# 10_-_ETHERNET.net
KiCad netlist of a schematic drawn in Altium Designer
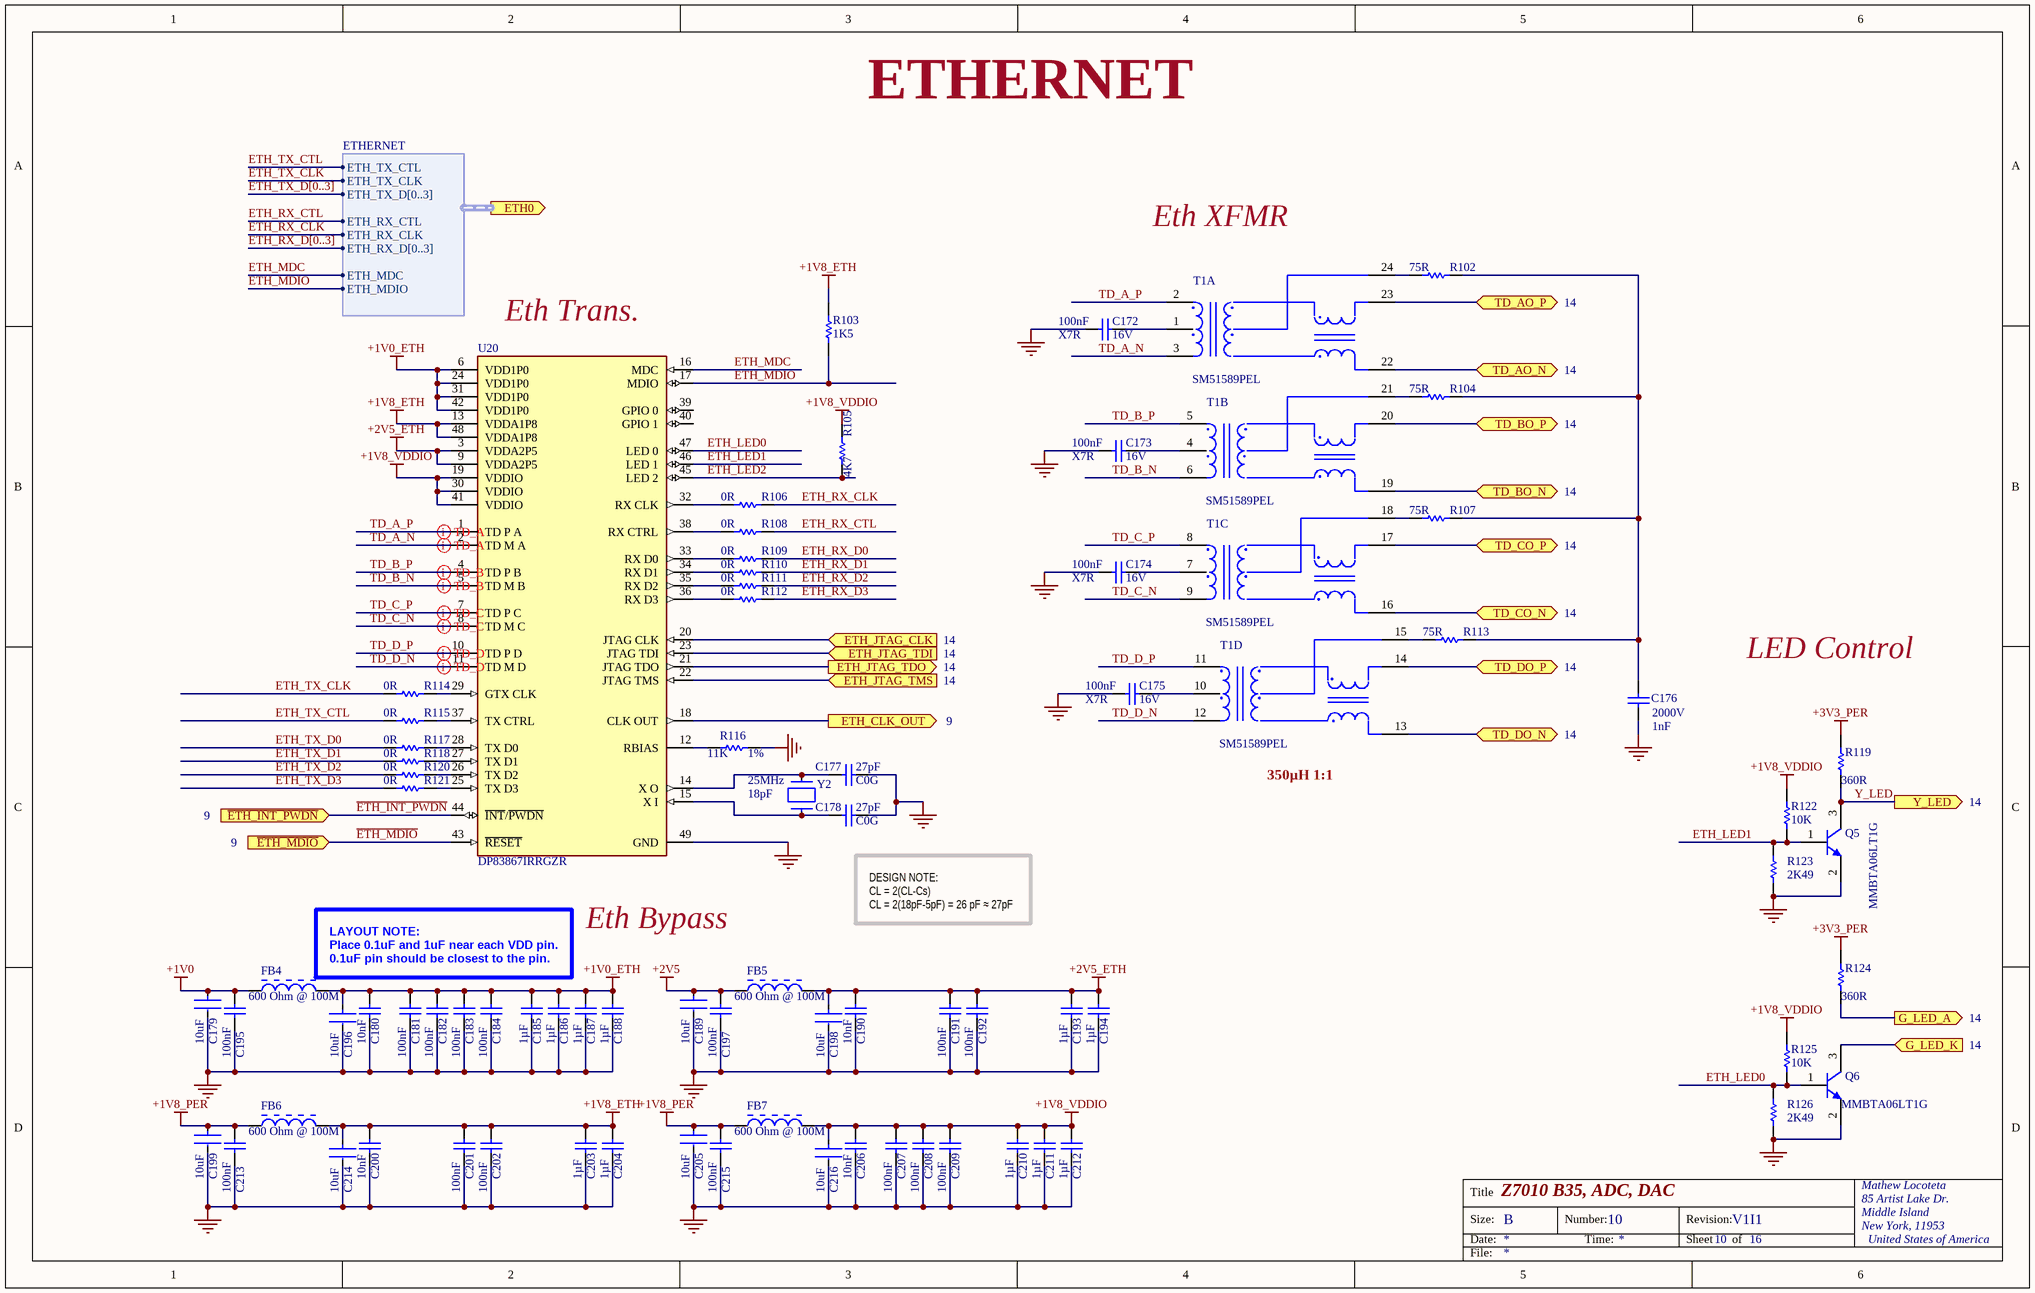
[diagram p0: [10] - ETHERNET.SchDoc]

(export (version "E")
  (design (tool "Eeschema 10.0.6"))
  (components
    (comp (ref "C172")
      (value "100nF 0402 16V")
      (fields
        (field (name "MANUFACTURER") "KEMET")
        (field (name "MANUFACTURER PART NUMBER") "C0402C104J4RACTU")
        (field (name "TOLERANCE") "5%")
        (field (name "DIELECTRIC") "X7R")
        (field (name "VOLTAGE RATING") "16V")
        (field (name "CAPACITANCE") "100nF")
      )
      (libsource (lib "Zynq 7000") (part "C0402C104J4RACTU"))
    )
    (comp (ref "C173")
      (value "100nF 0402 16V")
      (fields
        (field (name "MANUFACTURER") "KEMET")
        (field (name "MANUFACTURER PART NUMBER") "C0402C104J4RACTU")
        (field (name "TOLERANCE") "5%")
        (field (name "DIELECTRIC") "X7R")
        (field (name "VOLTAGE RATING") "16V")
        (field (name "CAPACITANCE") "100nF")
      )
      (libsource (lib "Zynq 7000") (part "C0402C104J4RACTU"))
    )
    (comp (ref "C174")
      (value "100nF 0402 16V")
      (fields
        (field (name "MANUFACTURER") "KEMET")
        (field (name "MANUFACTURER PART NUMBER") "C0402C104J4RACTU")
        (field (name "TOLERANCE") "5%")
        (field (name "DIELECTRIC") "X7R")
        (field (name "VOLTAGE RATING") "16V")
        (field (name "CAPACITANCE") "100nF")
      )
      (libsource (lib "Zynq 7000") (part "C0402C104J4RACTU"))
    )
    (comp (ref "C175")
      (value "100nF 0402 16V")
      (fields
        (field (name "MANUFACTURER") "KEMET")
        (field (name "MANUFACTURER PART NUMBER") "C0402C104J4RACTU")
        (field (name "TOLERANCE") "5%")
        (field (name "DIELECTRIC") "X7R")
        (field (name "VOLTAGE RATING") "16V")
        (field (name "CAPACITANCE") "100nF")
      )
      (libsource (lib "Zynq 7000") (part "C0402C104J4RACTU"))
    )
    (comp (ref "C176")
      (value "1808GC102KAT1A")
      (footprint "CAPC4620X180X75LL50T35")
      (description "Chip Capacitor, 1000 pF, +/- 10%, 2000 V, -55 to 125 degC, 1808 (4520 Metric), RoHS, Tape and Reel")
      (fields
        (field (name "MANUFACTURER") "AVX")
        (field (name "RATED VOLTAGE") "2000V")
        (field (name "CAPACITANCE") "1nF")
      )
      (libsource (lib "Altium Content Vault") (part "CAP-NP-2"))
    )
    (comp (ref "C177")
      (value "27pF")
      (footprint "CAPC0402(1005)60_M")
      (description "CAP 27pF 50V ±5% 0402 (1005 Metric) Thickness 0.6mm SMD")
      (fields
        (field (name "TOLERANCE") "Â±5%")
        (field (name "DIELECCTRIC") "C0G")
        (field (name "Comment") "CAP 27pF 50V 0402(1005)")
      )
      (libsource (lib "Altium Content Vault") (part "CAP"))
    )
    (comp (ref "C178")
      (value "27pF")
      (footprint "CAPC0402(1005)60_M")
      (description "CAP 27pF 50V ±5% 0402 (1005 Metric) Thickness 0.6mm SMD")
      (fields
        (field (name "TOLERANCE") "Â±5%")
        (field (name "DIELECCTRIC") "C0G")
        (field (name "Comment") "CAP 27pF 50V 0402(1005)")
      )
      (libsource (lib "Altium Content Vault") (part "CAP"))
    )
    (comp (ref "C179")
      (value "CL05A106MP8NUB8")
      (footprint "FP-CL07-IPC_C")
      (description "Cap Ceramic 10uF 10V X5R ±20% SMD 0402 +85°C Paper T/R")
      (fields (field (name "CAPACITANCE") "10uF") (field (name "TOLERANCE") "20%"))
      (libsource (lib "Altium Content Vault") (part "b4654b650e69147ec39a6b967a45e02"))
    )
    (comp (ref "C180")
      (value "10nF 16V 0402 X7R")
      (fields
        (field (name "MANUFACTURER") "KEMET")
        (field (name "MANUFACTURER PART NUMBER") "C0402C103J4RACTU")
        (field (name "TOLERANCE") "5%")
        (field (name "CAPACITANCE") "10nF")
      )
      (libsource (lib "Zynq 7000") (part "C0402C103J4RACTU"))
    )
    (comp (ref "C181")
      (value "100nF 0402 16V")
      (fields
        (field (name "MANUFACTURER") "KEMET")
        (field (name "MANUFACTURER PART NUMBER") "C0402C104J4RACTU")
        (field (name "TOLERANCE") "5%")
        (field (name "CAPACITANCE") "100nF")
      )
      (libsource (lib "Zynq 7000") (part "C0402C104J4RACTU"))
    )
    (comp (ref "C182")
      (value "100nF 0402 16V")
      (fields
        (field (name "MANUFACTURER") "KEMET")
        (field (name "MANUFACTURER PART NUMBER") "C0402C104J4RACTU")
        (field (name "TOLERANCE") "5%")
        (field (name "CAPACITANCE") "100nF")
      )
      (libsource (lib "Zynq 7000") (part "C0402C104J4RACTU"))
    )
    (comp (ref "C183")
      (value "100nF 0402 16V")
      (fields
        (field (name "MANUFACTURER") "KEMET")
        (field (name "MANUFACTURER PART NUMBER") "C0402C104J4RACTU")
        (field (name "TOLERANCE") "5%")
        (field (name "CAPACITANCE") "100nF")
      )
      (libsource (lib "Zynq 7000") (part "C0402C104J4RACTU"))
    )
    (comp (ref "C184")
      (value "100nF 0402 16V")
      (fields
        (field (name "MANUFACTURER") "KEMET")
        (field (name "MANUFACTURER PART NUMBER") "C0402C104J4RACTU")
        (field (name "TOLERANCE") "5%")
        (field (name "CAPACITANCE") "100nF")
      )
      (libsource (lib "Zynq 7000") (part "C0402C104J4RACTU"))
    )
    (comp (ref "C185")
      (value "1µF")
      (footprint "CAPC1005X60X30LL05T10")
      (fields (field (name "PART NUMBER") "C0402C105K8PAC7867") (field (name "MANUFACTURER") "Kemet"))
      (libsource (lib "Altium Content Vault") (part "CAP"))
    )
    (comp (ref "C186")
      (value "1µF")
      (footprint "CAPC1005X60X30LL05T10")
      (fields (field (name "PART NUMBER") "C0402C105K8PAC7867") (field (name "MANUFACTURER") "Kemet"))
      (libsource (lib "Altium Content Vault") (part "CAP"))
    )
    (comp (ref "C187")
      (value "1µF")
      (footprint "CAPC1005X60X30LL05T10")
      (fields (field (name "PART NUMBER") "C0402C105K8PAC7867") (field (name "MANUFACTURER") "Kemet"))
      (libsource (lib "Altium Content Vault") (part "CAP"))
    )
    (comp (ref "C188")
      (value "1µF")
      (footprint "CAPC1005X60X30LL05T10")
      (fields (field (name "PART NUMBER") "C0402C105K8PAC7867") (field (name "MANUFACTURER") "Kemet"))
      (libsource (lib "Altium Content Vault") (part "CAP"))
    )
    (comp (ref "C189")
      (value "CL05A106MP8NUB8")
      (footprint "FP-CL07-IPC_C")
      (description "Cap Ceramic 10uF 10V X5R ±20% SMD 0402 +85°C Paper T/R")
      (fields (field (name "CAPACITANCE") "10uF") (field (name "TOLERANCE") "20%"))
      (libsource (lib "Altium Content Vault") (part "b4654b650e69147ec39a6b967a45e02"))
    )
    (comp (ref "C190")
      (value "10nF 16V 0402 X7R")
      (fields
        (field (name "MANUFACTURER") "KEMET")
        (field (name "MANUFACTURER PART NUMBER") "C0402C103J4RACTU")
        (field (name "TOLERANCE") "5%")
        (field (name "CAPACITANCE") "10nF")
      )
      (libsource (lib "Zynq 7000") (part "C0402C103J4RACTU"))
    )
    (comp (ref "C191")
      (value "100nF 0402 16V")
      (fields
        (field (name "MANUFACTURER") "KEMET")
        (field (name "MANUFACTURER PART NUMBER") "C0402C104J4RACTU")
        (field (name "TOLERANCE") "5%")
        (field (name "CAPACITANCE") "100nF")
      )
      (libsource (lib "Zynq 7000") (part "C0402C104J4RACTU"))
    )
    (comp (ref "C192")
      (value "100nF 0402 16V")
      (fields
        (field (name "MANUFACTURER") "KEMET")
        (field (name "MANUFACTURER PART NUMBER") "C0402C104J4RACTU")
        (field (name "TOLERANCE") "5%")
        (field (name "CAPACITANCE") "100nF")
      )
      (libsource (lib "Zynq 7000") (part "C0402C104J4RACTU"))
    )
    (comp (ref "C193")
      (value "1µF")
      (footprint "CAPC1005X60X30LL05T10")
      (fields (field (name "PART NUMBER") "C0402C105K8PAC7867") (field (name "MANUFACTURER") "Kemet"))
      (libsource (lib "Altium Content Vault") (part "CAP"))
    )
    (comp (ref "C194")
      (value "1µF")
      (footprint "CAPC1005X60X30LL05T10")
      (fields (field (name "PART NUMBER") "C0402C105K8PAC7867") (field (name "MANUFACTURER") "Kemet"))
      (libsource (lib "Altium Content Vault") (part "CAP"))
    )
    (comp (ref "C195")
      (value "100nF 0402 16V")
      (fields
        (field (name "MANUFACTURER") "KEMET")
        (field (name "MANUFACTURER PART NUMBER") "C0402C104J4RACTU")
        (field (name "TOLERANCE") "5%")
        (field (name "CAPACITANCE") "100nF")
      )
      (libsource (lib "Zynq 7000") (part "C0402C104J4RACTU"))
    )
    (comp (ref "C196")
      (value "CL05A106MP8NUB8")
      (footprint "FP-CL07-IPC_C")
      (description "Cap Ceramic 10uF 10V X5R ±20% SMD 0402 +85°C Paper T/R")
      (fields (field (name "CAPACITANCE") "10uF") (field (name "TOLERANCE") "20%"))
      (libsource (lib "Altium Content Vault") (part "b4654b650e69147ec39a6b967a45e02"))
    )
    (comp (ref "C197")
      (value "100nF 0402 16V")
      (fields
        (field (name "MANUFACTURER") "KEMET")
        (field (name "MANUFACTURER PART NUMBER") "C0402C104J4RACTU")
        (field (name "TOLERANCE") "5%")
        (field (name "CAPACITANCE") "100nF")
      )
      (libsource (lib "Zynq 7000") (part "C0402C104J4RACTU"))
    )
    (comp (ref "C198")
      (value "CL05A106MP8NUB8")
      (footprint "FP-CL07-IPC_C")
      (description "Cap Ceramic 10uF 10V X5R ±20% SMD 0402 +85°C Paper T/R")
      (fields (field (name "CAPACITANCE") "10uF") (field (name "TOLERANCE") "20%"))
      (libsource (lib "Altium Content Vault") (part "b4654b650e69147ec39a6b967a45e02"))
    )
    (comp (ref "C199")
      (value "CL05A106MP8NUB8")
      (footprint "FP-CL07-IPC_C")
      (description "Cap Ceramic 10uF 10V X5R ±20% SMD 0402 +85°C Paper T/R")
      (fields (field (name "CAPACITANCE") "10uF") (field (name "TOLERANCE") "20%"))
      (libsource (lib "Altium Content Vault") (part "b4654b650e69147ec39a6b967a45e02"))
    )
    (comp (ref "C200")
      (value "10nF 16V 0402 X7R")
      (fields
        (field (name "MANUFACTURER") "KEMET")
        (field (name "MANUFACTURER PART NUMBER") "C0402C103J4RACTU")
        (field (name "TOLERANCE") "5%")
        (field (name "CAPACITANCE") "10nF")
      )
      (libsource (lib "Zynq 7000") (part "C0402C103J4RACTU"))
    )
    (comp (ref "C201")
      (value "100nF 0402 16V")
      (fields
        (field (name "MANUFACTURER") "KEMET")
        (field (name "MANUFACTURER PART NUMBER") "C0402C104J4RACTU")
        (field (name "TOLERANCE") "5%")
        (field (name "CAPACITANCE") "100nF")
      )
      (libsource (lib "Zynq 7000") (part "C0402C104J4RACTU"))
    )
    (comp (ref "C202")
      (value "100nF 0402 16V")
      (fields
        (field (name "MANUFACTURER") "KEMET")
        (field (name "MANUFACTURER PART NUMBER") "C0402C104J4RACTU")
        (field (name "TOLERANCE") "5%")
        (field (name "CAPACITANCE") "100nF")
      )
      (libsource (lib "Zynq 7000") (part "C0402C104J4RACTU"))
    )
    (comp (ref "C203")
      (value "1µF")
      (footprint "CAPC1005X60X30LL05T10")
      (fields (field (name "PART NUMBER") "C0402C105K8PAC7867") (field (name "MANUFACTURER") "Kemet"))
      (libsource (lib "Altium Content Vault") (part "CAP"))
    )
    (comp (ref "C204")
      (value "1µF")
      (footprint "CAPC1005X60X30LL05T10")
      (fields (field (name "PART NUMBER") "C0402C105K8PAC7867") (field (name "MANUFACTURER") "Kemet"))
      (libsource (lib "Altium Content Vault") (part "CAP"))
    )
    (comp (ref "C205")
      (value "CL05A106MP8NUB8")
      (footprint "FP-CL07-IPC_C")
      (description "Cap Ceramic 10uF 10V X5R ±20% SMD 0402 +85°C Paper T/R")
      (fields (field (name "CAPACITANCE") "10uF") (field (name "TOLERANCE") "20%"))
      (libsource (lib "Altium Content Vault") (part "b4654b650e69147ec39a6b967a45e02"))
    )
    (comp (ref "C206")
      (value "10nF 16V 0402 X7R")
      (fields
        (field (name "MANUFACTURER") "KEMET")
        (field (name "MANUFACTURER PART NUMBER") "C0402C103J4RACTU")
        (field (name "TOLERANCE") "5%")
        (field (name "CAPACITANCE") "10nF")
      )
      (libsource (lib "Zynq 7000") (part "C0402C103J4RACTU"))
    )
    (comp (ref "C207")
      (value "100nF 0402 16V")
      (fields
        (field (name "MANUFACTURER") "KEMET")
        (field (name "MANUFACTURER PART NUMBER") "C0402C104J4RACTU")
        (field (name "TOLERANCE") "5%")
        (field (name "CAPACITANCE") "100nF")
      )
      (libsource (lib "Zynq 7000") (part "C0402C104J4RACTU"))
    )
    (comp (ref "C208")
      (value "100nF 0402 16V")
      (fields
        (field (name "MANUFACTURER") "KEMET")
        (field (name "MANUFACTURER PART NUMBER") "C0402C104J4RACTU")
        (field (name "TOLERANCE") "5%")
        (field (name "CAPACITANCE") "100nF")
      )
      (libsource (lib "Zynq 7000") (part "C0402C104J4RACTU"))
    )
    (comp (ref "C209")
      (value "100nF 0402 16V")
      (fields
        (field (name "MANUFACTURER") "KEMET")
        (field (name "MANUFACTURER PART NUMBER") "C0402C104J4RACTU")
        (field (name "TOLERANCE") "5%")
        (field (name "CAPACITANCE") "100nF")
      )
      (libsource (lib "Zynq 7000") (part "C0402C104J4RACTU"))
    )
    (comp (ref "C210")
      (value "1µF")
      (footprint "CAPC1005X60X30LL05T10")
      (fields (field (name "PART NUMBER") "C0402C105K8PAC7867") (field (name "MANUFACTURER") "Kemet"))
      (libsource (lib "Altium Content Vault") (part "CAP"))
    )
    (comp (ref "C211")
      (value "1µF")
      (footprint "CAPC1005X60X30LL05T10")
      (fields (field (name "PART NUMBER") "C0402C105K8PAC7867") (field (name "MANUFACTURER") "Kemet"))
      (libsource (lib "Altium Content Vault") (part "CAP"))
    )
    (comp (ref "C212")
      (value "1µF")
      (footprint "CAPC1005X60X30LL05T10")
      (fields (field (name "PART NUMBER") "C0402C105K8PAC7867") (field (name "MANUFACTURER") "Kemet"))
      (libsource (lib "Altium Content Vault") (part "CAP"))
    )
    (comp (ref "C213")
      (value "100nF 0402 16V")
      (fields
        (field (name "MANUFACTURER") "KEMET")
        (field (name "MANUFACTURER PART NUMBER") "C0402C104J4RACTU")
        (field (name "TOLERANCE") "5%")
        (field (name "CAPACITANCE") "100nF")
      )
      (libsource (lib "Zynq 7000") (part "C0402C104J4RACTU"))
    )
    (comp (ref "C214")
      (value "CL05A106MP8NUB8")
      (footprint "FP-CL07-IPC_C")
      (description "Cap Ceramic 10uF 10V X5R ±20% SMD 0402 +85°C Paper T/R")
      (fields (field (name "CAPACITANCE") "10uF") (field (name "TOLERANCE") "20%"))
      (libsource (lib "Altium Content Vault") (part "b4654b650e69147ec39a6b967a45e02"))
    )
    (comp (ref "C215")
      (value "100nF 0402 16V")
      (fields
        (field (name "MANUFACTURER") "KEMET")
        (field (name "MANUFACTURER PART NUMBER") "C0402C104J4RACTU")
        (field (name "TOLERANCE") "5%")
        (field (name "CAPACITANCE") "100nF")
      )
      (libsource (lib "Zynq 7000") (part "C0402C104J4RACTU"))
    )
    (comp (ref "C216")
      (value "CL05A106MP8NUB8")
      (footprint "FP-CL07-IPC_C")
      (description "Cap Ceramic 10uF 10V X5R ±20% SMD 0402 +85°C Paper T/R")
      (fields (field (name "CAPACITANCE") "10uF") (field (name "TOLERANCE") "20%"))
      (libsource (lib "Altium Content Vault") (part "b4654b650e69147ec39a6b967a45e02"))
    )
    (comp (ref "FB4")
      (value "BLM18HE601SN1D")
      (footprint "MURA-BLM18-RF-H4-CHIP-2_V")
      (fields (field (name "MANUFACTURER") "Murata") (field (name "IMPEDANCE (AT 100 MHZ)") "600 Ohm @ 100M"))
      (libsource (lib "Altium Content Vault") (part "MURA-FB-2"))
    )
    (comp (ref "FB5")
      (value "BLM18HE601SN1D")
      (footprint "MURA-BLM18-RF-H4-CHIP-2_V")
      (fields (field (name "MANUFACTURER") "Murata") (field (name "IMPEDANCE (AT 100 MHZ)") "600 Ohm @ 100M"))
      (libsource (lib "Altium Content Vault") (part "MURA-FB-2"))
    )
    (comp (ref "FB6")
      (value "BLM18HE601SN1D")
      (footprint "MURA-BLM18-RF-H4-CHIP-2_V")
      (fields (field (name "MANUFACTURER") "Murata") (field (name "IMPEDANCE (AT 100 MHZ)") "600 Ohm @ 100M"))
      (libsource (lib "Altium Content Vault") (part "MURA-FB-2"))
    )
    (comp (ref "FB7")
      (value "BLM18HE601SN1D")
      (footprint "MURA-BLM18-RF-H4-CHIP-2_V")
      (fields (field (name "MANUFACTURER") "Murata") (field (name "IMPEDANCE (AT 100 MHZ)") "600 Ohm @ 100M"))
      (libsource (lib "Altium Content Vault") (part "MURA-FB-2"))
    )
    (comp (ref "Q5")
      (value "MMBTA06LT1G")
      (footprint "ONSC-SOT-23-3-318-08_V")
      (description "Driver Transistor, NPN Silicon, 3-Pin SOT-23, Pb-Free, Tape and Reel")
      (fields (field (name "MANUFACTURER") "On Semiconductor"))
      (libsource (lib "Altium Content Vault") (part "ONSC-NPN-B1E2C3-3"))
    )
    (comp (ref "Q6")
      (value "MMBTA06LT1G")
      (footprint "ONSC-SOT-23-3-318-08_V")
      (description "Driver Transistor, NPN Silicon, 3-Pin SOT-23, Pb-Free, Tape and Reel")
      (fields (field (name "MANUFACTURER") "On Semiconductor"))
      (libsource (lib "Altium Content Vault") (part "ONSC-NPN-B1E2C3-3"))
    )
    (comp (ref "R102")
      (value "75R 0805")
      (fields
        (field (name "MANUFACTURER") "Vishay")
        (field (name "MANUFACTURER PART NUMBER") "CRCW080575R0FKEA")
        (field (name "TOLERANCE") "1%")
        (field (name "RESISTANCE") "75R")
      )
      (libsource (lib "Zynq 7000") (part "CRCW080575R0FKEA"))
    )
    (comp (ref "R103")
      (value "1K5")
      (footprint "RESC1005X40X25NL05T05")
      (fields (field (name "PART NUMBER") "CRCW04021K50FKED") (field (name "MANUFACTURER") "Vishay Dale"))
      (libsource (lib "Altium Content Vault") (part "RES"))
    )
    (comp (ref "R104")
      (value "75R 0805")
      (fields
        (field (name "MANUFACTURER") "Vishay")
        (field (name "MANUFACTURER PART NUMBER") "CRCW080575R0FKEA")
        (field (name "TOLERANCE") "1%")
        (field (name "RESISTANCE") "75R")
      )
      (libsource (lib "Zynq 7000") (part "CRCW080575R0FKEA"))
    )
    (comp (ref "R105")
      (value "4K7 0402 1%")
      (description "Resistor SMD 4.7 kOhm 0402 PU=10000 ST, CRCW04024K70FKED, Vishay")
      (fields
        (field (name "MANUFACTURER") "Vishay")
        (field (name "MANUFACTURER PART NUMBER") "CRCW04024K70FKED")
        (field (name "RESISTANCE") "4K7")
      )
      (libsource (lib "Zynq 7000") (part "CRCW04024K70FKED"))
    )
    (comp (ref "R106")
      (value "0R")
      (footprint "RESC1005X40X25ML05T10")
      (fields (field (name "PART NUMBER") "CRCW04020000Z0EDHP") (field (name "MANUFACTURER") "Vishay Dale"))
      (libsource (lib "Altium Content Vault") (part "RES"))
    )
    (comp (ref "R107")
      (value "75R 0805")
      (fields
        (field (name "MANUFACTURER") "Vishay")
        (field (name "MANUFACTURER PART NUMBER") "CRCW080575R0FKEA")
        (field (name "TOLERANCE") "1%")
        (field (name "RESISTANCE") "75R")
      )
      (libsource (lib "Zynq 7000") (part "CRCW080575R0FKEA"))
    )
    (comp (ref "R108")
      (value "0R")
      (footprint "RESC1005X40X25ML05T10")
      (fields (field (name "PART NUMBER") "CRCW04020000Z0EDHP") (field (name "MANUFACTURER") "Vishay Dale"))
      (libsource (lib "Altium Content Vault") (part "RES"))
    )
    (comp (ref "R109")
      (value "0R")
      (footprint "RESC1005X40X25ML05T10")
      (fields (field (name "PART NUMBER") "CRCW04020000Z0EDHP") (field (name "MANUFACTURER") "Vishay Dale"))
      (libsource (lib "Altium Content Vault") (part "RES"))
    )
    (comp (ref "R110")
      (value "0R")
      (footprint "RESC1005X40X25ML05T10")
      (fields (field (name "PART NUMBER") "CRCW04020000Z0EDHP") (field (name "MANUFACTURER") "Vishay Dale"))
      (libsource (lib "Altium Content Vault") (part "RES"))
    )
    (comp (ref "R111")
      (value "0R")
      (footprint "RESC1005X40X25ML05T10")
      (fields (field (name "PART NUMBER") "CRCW04020000Z0EDHP") (field (name "MANUFACTURER") "Vishay Dale"))
      (libsource (lib "Altium Content Vault") (part "RES"))
    )
    (comp (ref "R112")
      (value "0R")
      (footprint "RESC1005X40X25ML05T10")
      (fields (field (name "PART NUMBER") "CRCW04020000Z0EDHP") (field (name "MANUFACTURER") "Vishay Dale"))
      (libsource (lib "Altium Content Vault") (part "RES"))
    )
    (comp (ref "R113")
      (value "75R 0805")
      (fields
        (field (name "MANUFACTURER") "Vishay")
        (field (name "MANUFACTURER PART NUMBER") "CRCW080575R0FKEA")
        (field (name "TOLERANCE") "1%")
        (field (name "RESISTANCE") "75R")
      )
      (libsource (lib "Zynq 7000") (part "CRCW080575R0FKEA"))
    )
    (comp (ref "R114")
      (value "0R")
      (footprint "RESC1005X40X25ML05T10")
      (fields (field (name "PART NUMBER") "CRCW04020000Z0EDHP") (field (name "MANUFACTURER") "Vishay Dale"))
      (libsource (lib "Altium Content Vault") (part "RES"))
    )
    (comp (ref "R115")
      (value "0R")
      (footprint "RESC1005X40X25ML05T10")
      (fields (field (name "PART NUMBER") "CRCW04020000Z0EDHP") (field (name "MANUFACTURER") "Vishay Dale"))
      (libsource (lib "Altium Content Vault") (part "RES"))
    )
    (comp (ref "R116")
      (value "11K")
      (footprint "RESC1005X40X25NL05T05")
      (fields
        (field (name "MANUFACTURER") "Vishay Dale")
        (field (name "PART NUMBER") "CRCW040211K0FKED")
        (field (name "TOLERANCE") "1%")
      )
      (libsource (lib "Altium Content Vault") (part "RES"))
    )
    (comp (ref "R117")
      (value "0R")
      (footprint "RESC1005X40X25ML05T10")
      (fields (field (name "PART NUMBER") "CRCW04020000Z0EDHP") (field (name "MANUFACTURER") "Vishay Dale"))
      (libsource (lib "Altium Content Vault") (part "RES"))
    )
    (comp (ref "R118")
      (value "0R")
      (footprint "RESC1005X40X25ML05T10")
      (fields (field (name "PART NUMBER") "CRCW04020000Z0EDHP") (field (name "MANUFACTURER") "Vishay Dale"))
      (libsource (lib "Altium Content Vault") (part "RES"))
    )
    (comp (ref "R119")
      (value "360R")
      (footprint "RESC1005X40X25NL05T05")
      (fields (field (name "PART NUMBER") "CRCW0402360RFKED") (field (name "MANUFACTURER") "Vishay Dale"))
      (libsource (lib "Altium Content Vault") (part "RES"))
    )
    (comp (ref "R120")
      (value "0R")
      (footprint "RESC1005X40X25ML05T10")
      (fields (field (name "PART NUMBER") "CRCW04020000Z0EDHP") (field (name "MANUFACTURER") "Vishay Dale"))
      (libsource (lib "Altium Content Vault") (part "RES"))
    )
    (comp (ref "R121")
      (value "0R")
      (footprint "RESC1005X40X25ML05T10")
      (fields (field (name "PART NUMBER") "CRCW04020000Z0EDHP") (field (name "MANUFACTURER") "Vishay Dale"))
      (libsource (lib "Altium Content Vault") (part "RES"))
    )
    (comp (ref "R122")
      (value "10K")
      (footprint "RESC1005X40X25ML05T10")
      (fields (field (name "PART NUMBER") "CRCW040210K0FKEDHP") (field (name "MANUFACTURER") "Vishay Dale"))
      (libsource (lib "Altium Content Vault") (part "RES"))
    )
    (comp (ref "R123")
      (value "2K49")
      (footprint "RESC1005X40X25ML05T05")
      (fields (field (name "MANUFACTURER") "Vishay Dale") (field (name "PART NUMBER") "CRCW04022K49FKTD"))
      (libsource (lib "Altium Content Vault") (part "RES"))
    )
    (comp (ref "R124")
      (value "360R")
      (footprint "RESC1005X40X25NL05T05")
      (fields (field (name "PART NUMBER") "CRCW0402360RFKED") (field (name "MANUFACTURER") "Vishay Dale"))
      (libsource (lib "Altium Content Vault") (part "RES"))
    )
    (comp (ref "R125")
      (value "10K")
      (footprint "RESC1005X40X25ML05T10")
      (fields (field (name "PART NUMBER") "CRCW040210K0FKEDHP") (field (name "MANUFACTURER") "Vishay Dale"))
      (libsource (lib "Altium Content Vault") (part "RES"))
    )
    (comp (ref "R126")
      (value "2K49")
      (footprint "RESC1005X40X25ML05T05")
      (fields (field (name "MANUFACTURER") "Vishay Dale") (field (name "PART NUMBER") "CRCW04022K49FKTD"))
      (libsource (lib "Altium Content Vault") (part "RES"))
    )
    (comp (ref "T1")
      (value "SM51589PEL")
      (footprint "FP-SM51589PEL-MFG")
      (description "PULSE XFMR 1CT:1CT 350UH")
      (fields
        (field (name "MANUFACTURER") "Bourns")
        (field (name "OCTOPART") "https://octopart.com/sm51589pel-bourns-49272966")
      )
      (libsource (lib "Altium Content Vault") (part "7d3984cf9a79bfa00557e622709ad5e"))
    )
    (comp (ref "U20")
      (value "DP83867IRRGZR")
      (footprint "FP-RGZ0048B-MFG")
      (description "IC ETHERNET PHY 48VQFN")
      (fields
        (field (name "OCTOPART") "https://octopart.com/dp83867irrgzr-texas+instruments-61842583")
        (field (name "MANUFACTURER") "Texas Instruments")
      )
      (libsource (lib "Altium Content Vault") (part "7b56164ef0af00af3f68235ebdc67f6"))
    )
    (comp (ref "Y2")
      (value "7A-25.000MAAJ-T")
      (footprint "FP-7A-MFG")
      (description "CRYSTAL 25.0000MHZ 18PF SMD")
      (fields
        (field (name "LOAD CAPACITANCE") "18pF")
        (field (name "FREQUENCY") "25MHz")
        (field (name "TOLERANCE") "30ppm")
      )
      (libsource (lib "Altium Content Vault") (part "c23a69dc6c9e2f18f2079038eb95dd1"))
    )
  )
  (nets
    (net (code "2") (name "+1V0") (class "Default")
      (node (ref "C179") (pin "1") (pinfunction "1_1") (pintype "passive"))
      (node (ref "C195") (pin "2") (pinfunction "2_2") (pintype "passive"))
      (node (ref "FB4") (pin "1") (pinfunction "1_1") (pintype "passive"))
    )
    (net (code "3") (name "+1V0_ETH") (class "Default")
      (node (ref "C180") (pin "2") (pinfunction "2_2") (pintype "passive"))
      (node (ref "C181") (pin "2") (pinfunction "2_2") (pintype "passive"))
      (node (ref "C182") (pin "2") (pinfunction "2_2") (pintype "passive"))
      (node (ref "C183") (pin "2") (pinfunction "2_2") (pintype "passive"))
      (node (ref "C184") (pin "2") (pinfunction "2_2") (pintype "passive"))
      (node (ref "C185") (pin "2") (pinfunction "2_2") (pintype "passive"))
      (node (ref "C186") (pin "2") (pinfunction "2_2") (pintype "passive"))
      (node (ref "C187") (pin "2") (pinfunction "2_2") (pintype "passive"))
      (node (ref "C188") (pin "2") (pinfunction "2_2") (pintype "passive"))
      (node (ref "C196") (pin "1") (pinfunction "1_1") (pintype "passive"))
      (node (ref "FB4") (pin "2") (pinfunction "2_2") (pintype "passive"))
      (node (ref "U20") (pin "24") (pinfunction "VDD1P0_24") (pintype "power_in"))
      (node (ref "U20") (pin "31") (pinfunction "VDD1P0_31") (pintype "power_in"))
      (node (ref "U20") (pin "42") (pinfunction "VDD1P0_42") (pintype "power_in"))
      (node (ref "U20") (pin "6") (pinfunction "VDD1P0_6") (pintype "power_in"))
    )
    (net (code "4") (name "+1V8_ETH") (class "Default")
      (node (ref "C200") (pin "2") (pinfunction "2_2") (pintype "passive"))
      (node (ref "C201") (pin "2") (pinfunction "2_2") (pintype "passive"))
      (node (ref "C202") (pin "2") (pinfunction "2_2") (pintype "passive"))
      (node (ref "C203") (pin "2") (pinfunction "2_2") (pintype "passive"))
      (node (ref "C204") (pin "2") (pinfunction "2_2") (pintype "passive"))
      (node (ref "C214") (pin "1") (pinfunction "1_1") (pintype "passive"))
      (node (ref "FB6") (pin "2") (pinfunction "2_2") (pintype "passive"))
      (node (ref "R103") (pin "2") (pinfunction "2_2") (pintype "passive"))
      (node (ref "U20") (pin "13") (pinfunction "VDDA1P8_13") (pintype "power_in"))
      (node (ref "U20") (pin "48") (pinfunction "VDDA1P8_48") (pintype "power_in"))
    )
    (net (code "5") (name "+1V8_PER") (class "Default")
      (node (ref "C199") (pin "1") (pinfunction "1_1") (pintype "passive"))
      (node (ref "C205") (pin "1") (pinfunction "1_1") (pintype "passive"))
      (node (ref "C213") (pin "2") (pinfunction "2_2") (pintype "passive"))
      (node (ref "C215") (pin "2") (pinfunction "2_2") (pintype "passive"))
      (node (ref "FB6") (pin "1") (pinfunction "1_1") (pintype "passive"))
      (node (ref "FB7") (pin "1") (pinfunction "1_1") (pintype "passive"))
    )
    (net (code "6") (name "+1V8_VDDIO") (class "Default")
      (node (ref "C206") (pin "2") (pinfunction "2_2") (pintype "passive"))
      (node (ref "C207") (pin "2") (pinfunction "2_2") (pintype "passive"))
      (node (ref "C208") (pin "2") (pinfunction "2_2") (pintype "passive"))
      (node (ref "C209") (pin "2") (pinfunction "2_2") (pintype "passive"))
      (node (ref "C210") (pin "2") (pinfunction "2_2") (pintype "passive"))
      (node (ref "C211") (pin "2") (pinfunction "2_2") (pintype "passive"))
      (node (ref "C212") (pin "2") (pinfunction "2_2") (pintype "passive"))
      (node (ref "C216") (pin "1") (pinfunction "1_1") (pintype "passive"))
      (node (ref "FB7") (pin "2") (pinfunction "2_2") (pintype "passive"))
      (node (ref "R105") (pin "2") (pinfunction "2_2") (pintype "passive"))
      (node (ref "R122") (pin "2") (pinfunction "2_2") (pintype "passive"))
      (node (ref "R125") (pin "2") (pinfunction "2_2") (pintype "passive"))
      (node (ref "U20") (pin "19") (pinfunction "VDDIO_19") (pintype "power_in"))
      (node (ref "U20") (pin "30") (pinfunction "VDDIO_30") (pintype "power_in"))
      (node (ref "U20") (pin "41") (pinfunction "VDDIO_41") (pintype "power_in"))
    )
    (net (code "7") (name "+2V5") (class "Default")
      (node (ref "C189") (pin "1") (pinfunction "1_1") (pintype "passive"))
      (node (ref "C197") (pin "2") (pinfunction "2_2") (pintype "passive"))
      (node (ref "FB5") (pin "1") (pinfunction "1_1") (pintype "passive"))
    )
    (net (code "8") (name "+2V5_ETH") (class "Default")
      (node (ref "C190") (pin "2") (pinfunction "2_2") (pintype "passive"))
      (node (ref "C191") (pin "2") (pinfunction "2_2") (pintype "passive"))
      (node (ref "C192") (pin "2") (pinfunction "2_2") (pintype "passive"))
      (node (ref "C193") (pin "2") (pinfunction "2_2") (pintype "passive"))
      (node (ref "C194") (pin "2") (pinfunction "2_2") (pintype "passive"))
      (node (ref "C198") (pin "1") (pinfunction "1_1") (pintype "passive"))
      (node (ref "FB5") (pin "2") (pinfunction "2_2") (pintype "passive"))
      (node (ref "U20") (pin "3") (pinfunction "VDDA2P5_3") (pintype "power_in"))
      (node (ref "U20") (pin "9") (pinfunction "VDDA2P5_9") (pintype "power_in"))
    )
    (net (code "9") (name "+3V3_PER") (class "Default")
      (node (ref "R119") (pin "2") (pinfunction "2_2") (pintype "passive"))
      (node (ref "R124") (pin "2") (pinfunction "2_2") (pintype "passive"))
    )
    (net (code "11") (name "/ETH_CLK_OUT") (class "Default")
      (node (ref "U20") (pin "18") (pinfunction "CLK_OUT_18") (pintype "output"))
    )
    (net (code "12") (name "/ETH_JTAG_CLK") (class "Default")
      (node (ref "U20") (pin "20") (pinfunction "JTAG_CLK_20") (pintype "input"))
    )
    (net (code "13") (name "/ETH_JTAG_TDI") (class "Default")
      (node (ref "U20") (pin "23") (pinfunction "JTAG_TDI_23") (pintype "input"))
    )
    (net (code "14") (name "/ETH_JTAG_TDO") (class "Default")
      (node (ref "U20") (pin "21") (pinfunction "JTAG_TDO_21") (pintype "output"))
    )
    (net (code "15") (name "/ETH_JTAG_TMS") (class "Default")
      (node (ref "U20") (pin "22") (pinfunction "JTAG_TMS_22") (pintype "input"))
    )
    (net (code "16") (name "/ETH_LED0") (class "Default")
      (node (ref "Q6") (pin "1") (pinfunction "B_1") (pintype "passive"))
      (node (ref "R125") (pin "1") (pinfunction "1_1") (pintype "passive"))
      (node (ref "R126") (pin "2") (pinfunction "2_2") (pintype "passive"))
      (node (ref "U20") (pin "47") (pinfunction "LED_0_47") (pintype "bidirectional"))
    )
    (net (code "17") (name "/ETH_LED1") (class "Default")
      (node (ref "Q5") (pin "1") (pinfunction "B_1") (pintype "passive"))
      (node (ref "R122") (pin "1") (pinfunction "1_1") (pintype "passive"))
      (node (ref "R123") (pin "2") (pinfunction "2_2") (pintype "passive"))
      (node (ref "U20") (pin "46") (pinfunction "LED_1_46") (pintype "bidirectional"))
    )
    (net (code "18") (name "/ETH_LED2") (class "Default")
      (node (ref "R105") (pin "1") (pinfunction "1_1") (pintype "passive"))
      (node (ref "U20") (pin "45") (pinfunction "LED_2_45") (pintype "bidirectional"))
    )
    (net (code "19") (name "/ETH_MDC") (class "Default")
      (node (ref "U20") (pin "16") (pinfunction "MDC_16") (pintype "input"))
    )
    (net (code "20") (name "/ETH_MDIO") (class "Default")
      (node (ref "R103") (pin "1") (pinfunction "1_1") (pintype "passive"))
      (node (ref "U20") (pin "17") (pinfunction "MDIO_17") (pintype "bidirectional"))
    )
    (net (code "21") (name "/ETH_RX_CLK") (class "Default")
      (node (ref "R106") (pin "2") (pinfunction "2_2") (pintype "passive"))
    )
    (net (code "22") (name "/ETH_RX_CTL") (class "Default")
      (node (ref "R108") (pin "2") (pinfunction "2_2") (pintype "passive"))
    )
    (net (code "23") (name "/ETH_RX_D0") (class "Default")
      (node (ref "R109") (pin "2") (pinfunction "2_2") (pintype "passive"))
    )
    (net (code "24") (name "/ETH_RX_D1") (class "Default")
      (node (ref "R110") (pin "2") (pinfunction "2_2") (pintype "passive"))
    )
    (net (code "25") (name "/ETH_RX_D2") (class "Default")
      (node (ref "R111") (pin "2") (pinfunction "2_2") (pintype "passive"))
    )
    (net (code "26") (name "/ETH_RX_D3") (class "Default")
      (node (ref "R112") (pin "2") (pinfunction "2_2") (pintype "passive"))
    )
    (net (code "28") (name "/ETH_TX_CLK") (class "Default")
      (node (ref "R114") (pin "1") (pinfunction "1_1") (pintype "passive"))
    )
    (net (code "29") (name "/ETH_TX_CTL") (class "Default")
      (node (ref "R115") (pin "1") (pinfunction "1_1") (pintype "passive"))
    )
    (net (code "30") (name "/ETH_TX_D0") (class "Default")
      (node (ref "R117") (pin "1") (pinfunction "1_1") (pintype "passive"))
    )
    (net (code "31") (name "/ETH_TX_D1") (class "Default")
      (node (ref "R118") (pin "1") (pinfunction "1_1") (pintype "passive"))
    )
    (net (code "32") (name "/ETH_TX_D2") (class "Default")
      (node (ref "R120") (pin "1") (pinfunction "1_1") (pintype "passive"))
    )
    (net (code "33") (name "/ETH_TX_D3") (class "Default")
      (node (ref "R121") (pin "1") (pinfunction "1_1") (pintype "passive"))
    )
    (net (code "34") (name "/G_LED_A") (class "Default")
      (node (ref "R124") (pin "1") (pinfunction "1_1") (pintype "passive"))
    )
    (net (code "35") (name "/G_LED_K") (class "Default")
      (node (ref "Q6") (pin "3") (pinfunction "C_3") (pintype "passive"))
    )
    (net (code "36") (name "/TD_AO_N") (class "Default")
      (node (ref "T1") (pin "22") (pinfunction "TD1-_22") (pintype "passive"))
    )
    (net (code "37") (name "/TD_AO_P") (class "Default")
      (node (ref "T1") (pin "23") (pinfunction "TD1+_23") (pintype "passive"))
    )
    (net (code "38") (name "/TD_A_N") (class "Default")
      (node (ref "T1") (pin "3") (pinfunction "MX1-_3") (pintype "passive"))
      (node (ref "U20") (pin "2") (pinfunction "TD_M_A_2") (pintype "passive"))
    )
    (net (code "39") (name "/TD_A_P") (class "Default")
      (node (ref "T1") (pin "2") (pinfunction "MX1+_2") (pintype "passive"))
      (node (ref "U20") (pin "1") (pinfunction "TD_P_A_1") (pintype "passive"))
    )
    (net (code "40") (name "/TD_BO_N") (class "Default")
      (node (ref "T1") (pin "19") (pinfunction "TD2-_19") (pintype "passive"))
    )
    (net (code "41") (name "/TD_BO_P") (class "Default")
      (node (ref "T1") (pin "20") (pinfunction "TD2+_20") (pintype "passive"))
    )
    (net (code "42") (name "/TD_B_N") (class "Default")
      (node (ref "T1") (pin "6") (pinfunction "MX2-_6") (pintype "passive"))
      (node (ref "U20") (pin "5") (pinfunction "TD_M_B_5") (pintype "passive"))
    )
    (net (code "43") (name "/TD_B_P") (class "Default")
      (node (ref "T1") (pin "5") (pinfunction "MX2+_5") (pintype "passive"))
      (node (ref "U20") (pin "4") (pinfunction "TD_P_B_4") (pintype "passive"))
    )
    (net (code "44") (name "/TD_CO_N") (class "Default")
      (node (ref "T1") (pin "16") (pinfunction "TD3-_16") (pintype "passive"))
    )
    (net (code "45") (name "/TD_CO_P") (class "Default")
      (node (ref "T1") (pin "17") (pinfunction "TD3+_17") (pintype "passive"))
    )
    (net (code "46") (name "/TD_C_N") (class "Default")
      (node (ref "T1") (pin "9") (pinfunction "MX3-_9") (pintype "passive"))
      (node (ref "U20") (pin "8") (pinfunction "TD_M_C_8") (pintype "passive"))
    )
    (net (code "47") (name "/TD_C_P") (class "Default")
      (node (ref "T1") (pin "8") (pinfunction "MX3+_8") (pintype "passive"))
      (node (ref "U20") (pin "7") (pinfunction "TD_P_C_7") (pintype "passive"))
    )
    (net (code "48") (name "/TD_DO_N") (class "Default")
      (node (ref "T1") (pin "13") (pinfunction "TD4-_13") (pintype "passive"))
    )
    (net (code "49") (name "/TD_DO_P") (class "Default")
      (node (ref "T1") (pin "14") (pinfunction "TD4+_14") (pintype "passive"))
    )
    (net (code "50") (name "/TD_D_N") (class "Default")
      (node (ref "T1") (pin "12") (pinfunction "MX4-_12") (pintype "passive"))
      (node (ref "U20") (pin "11") (pinfunction "TD_M_D_11") (pintype "passive"))
    )
    (net (code "51") (name "/TD_D_P") (class "Default")
      (node (ref "T1") (pin "11") (pinfunction "MX4+_11") (pintype "passive"))
      (node (ref "U20") (pin "10") (pinfunction "TD_P_D_10") (pintype "passive"))
    )
    (net (code "52") (name "/Y_LED") (class "Default")
      (node (ref "Q5") (pin "3") (pinfunction "C_3") (pintype "passive"))
      (node (ref "R119") (pin "1") (pinfunction "1_1") (pintype "passive"))
    )
    (net (code "54") (name "/~{ETH_INT_PWDN}") (class "Default")
      (node (ref "U20") (pin "44") (pinfunction "~{INT}/~{PWDN}_44") (pintype "bidirectional"))
    )
    (net (code "55") (name "/~{ETH_MDIO}") (class "Default")
      (node (ref "U20") (pin "43") (pinfunction "~{RESET}_43") (pintype "input"))
    )
    (net (code "56") (name "GND") (class "Default")
      (node (ref "C172") (pin "2") (pinfunction "2_2") (pintype "passive"))
      (node (ref "C173") (pin "2") (pinfunction "2_2") (pintype "passive"))
      (node (ref "C174") (pin "2") (pinfunction "2_2") (pintype "passive"))
      (node (ref "C175") (pin "2") (pinfunction "2_2") (pintype "passive"))
      (node (ref "C176") (pin "1") (pinfunction "1_1") (pintype "passive"))
      (node (ref "C177") (pin "2") (pinfunction "2_2") (pintype "passive"))
      (node (ref "C178") (pin "2") (pinfunction "2_2") (pintype "passive"))
      (node (ref "C179") (pin "2") (pinfunction "2_2") (pintype "passive"))
      (node (ref "C180") (pin "1") (pinfunction "1_1") (pintype "passive"))
      (node (ref "C181") (pin "1") (pinfunction "1_1") (pintype "passive"))
      (node (ref "C182") (pin "1") (pinfunction "1_1") (pintype "passive"))
      (node (ref "C183") (pin "1") (pinfunction "1_1") (pintype "passive"))
      (node (ref "C184") (pin "1") (pinfunction "1_1") (pintype "passive"))
      (node (ref "C185") (pin "1") (pinfunction "1_1") (pintype "passive"))
      (node (ref "C186") (pin "1") (pinfunction "1_1") (pintype "passive"))
      (node (ref "C187") (pin "1") (pinfunction "1_1") (pintype "passive"))
      (node (ref "C188") (pin "1") (pinfunction "1_1") (pintype "passive"))
      (node (ref "C189") (pin "2") (pinfunction "2_2") (pintype "passive"))
      (node (ref "C190") (pin "1") (pinfunction "1_1") (pintype "passive"))
      (node (ref "C191") (pin "1") (pinfunction "1_1") (pintype "passive"))
      (node (ref "C192") (pin "1") (pinfunction "1_1") (pintype "passive"))
      (node (ref "C193") (pin "1") (pinfunction "1_1") (pintype "passive"))
      (node (ref "C194") (pin "1") (pinfunction "1_1") (pintype "passive"))
      (node (ref "C195") (pin "1") (pinfunction "1_1") (pintype "passive"))
      (node (ref "C196") (pin "2") (pinfunction "2_2") (pintype "passive"))
      (node (ref "C197") (pin "1") (pinfunction "1_1") (pintype "passive"))
      (node (ref "C198") (pin "2") (pinfunction "2_2") (pintype "passive"))
      (node (ref "C199") (pin "2") (pinfunction "2_2") (pintype "passive"))
      (node (ref "C200") (pin "1") (pinfunction "1_1") (pintype "passive"))
      (node (ref "C201") (pin "1") (pinfunction "1_1") (pintype "passive"))
      (node (ref "C202") (pin "1") (pinfunction "1_1") (pintype "passive"))
      (node (ref "C203") (pin "1") (pinfunction "1_1") (pintype "passive"))
      (node (ref "C204") (pin "1") (pinfunction "1_1") (pintype "passive"))
      (node (ref "C205") (pin "2") (pinfunction "2_2") (pintype "passive"))
      (node (ref "C206") (pin "1") (pinfunction "1_1") (pintype "passive"))
      (node (ref "C207") (pin "1") (pinfunction "1_1") (pintype "passive"))
      (node (ref "C208") (pin "1") (pinfunction "1_1") (pintype "passive"))
      (node (ref "C209") (pin "1") (pinfunction "1_1") (pintype "passive"))
      (node (ref "C210") (pin "1") (pinfunction "1_1") (pintype "passive"))
      (node (ref "C211") (pin "1") (pinfunction "1_1") (pintype "passive"))
      (node (ref "C212") (pin "1") (pinfunction "1_1") (pintype "passive"))
      (node (ref "C213") (pin "1") (pinfunction "1_1") (pintype "passive"))
      (node (ref "C214") (pin "2") (pinfunction "2_2") (pintype "passive"))
      (node (ref "C215") (pin "1") (pinfunction "1_1") (pintype "passive"))
      (node (ref "C216") (pin "2") (pinfunction "2_2") (pintype "passive"))
      (node (ref "Q5") (pin "2") (pinfunction "E_2") (pintype "passive"))
      (node (ref "Q6") (pin "2") (pinfunction "E_2") (pintype "passive"))
      (node (ref "R116") (pin "1") (pinfunction "1_1") (pintype "passive"))
      (node (ref "R123") (pin "1") (pinfunction "1_1") (pintype "passive"))
      (node (ref "R126") (pin "1") (pinfunction "1_1") (pintype "passive"))
      (node (ref "U20") (pin "49") (pinfunction "GND_49") (pintype "power_in"))
    )
    (net (code "57") (name "Net-(C176-Pad2)") (class "Default")
      (node (ref "C176") (pin "2") (pinfunction "2_2") (pintype "passive"))
      (node (ref "R102") (pin "2") (pinfunction "2_2") (pintype "passive"))
      (node (ref "R104") (pin "2") (pinfunction "2_2") (pintype "passive"))
      (node (ref "R107") (pin "2") (pinfunction "2_2") (pintype "passive"))
      (node (ref "R113") (pin "2") (pinfunction "2_2") (pintype "passive"))
    )
    (net (code "58") (name "Net-(T1A-MCT1)") (class "Default")
      (node (ref "C172") (pin "1") (pinfunction "1_1") (pintype "passive"))
      (node (ref "T1") (pin "1") (pinfunction "MCT1_1") (pintype "passive"))
    )
    (net (code "59") (name "Net-(T1A-TCT1)") (class "Default")
      (node (ref "R102") (pin "1") (pinfunction "1_1") (pintype "passive"))
      (node (ref "T1") (pin "24") (pinfunction "TCT1_24") (pintype "passive"))
    )
    (net (code "60") (name "Net-(T1B-MCT2)") (class "Default")
      (node (ref "C173") (pin "1") (pinfunction "1_1") (pintype "passive"))
      (node (ref "T1") (pin "4") (pinfunction "MCT2_4") (pintype "passive"))
    )
    (net (code "61") (name "Net-(T1B-TCT2)") (class "Default")
      (node (ref "R104") (pin "1") (pinfunction "1_1") (pintype "passive"))
      (node (ref "T1") (pin "21") (pinfunction "TCT2_21") (pintype "passive"))
    )
    (net (code "62") (name "Net-(T1C-MCT3)") (class "Default")
      (node (ref "C174") (pin "1") (pinfunction "1_1") (pintype "passive"))
      (node (ref "T1") (pin "7") (pinfunction "MCT3_7") (pintype "passive"))
    )
    (net (code "63") (name "Net-(T1C-TCT3)") (class "Default")
      (node (ref "R107") (pin "1") (pinfunction "1_1") (pintype "passive"))
      (node (ref "T1") (pin "18") (pinfunction "TCT3_18") (pintype "passive"))
    )
    (net (code "64") (name "Net-(T1D-MCT4)") (class "Default")
      (node (ref "C175") (pin "1") (pinfunction "1_1") (pintype "passive"))
      (node (ref "T1") (pin "10") (pinfunction "MCT4_10") (pintype "passive"))
    )
    (net (code "65") (name "Net-(T1D-TCT4)") (class "Default")
      (node (ref "R113") (pin "1") (pinfunction "1_1") (pintype "passive"))
      (node (ref "T1") (pin "15") (pinfunction "TCT4_15") (pintype "passive"))
    )
    (net (code "66") (name "Net-(U20-GTX_CLK)") (class "Default")
      (node (ref "R114") (pin "2") (pinfunction "2_2") (pintype "passive"))
      (node (ref "U20") (pin "29") (pinfunction "GTX_CLK_29") (pintype "input"))
    )
    (net (code "67") (name "Net-(U20-RBIAS)") (class "Default")
      (node (ref "R116") (pin "2") (pinfunction "2_2") (pintype "passive"))
      (node (ref "U20") (pin "12") (pinfunction "RBIAS_12") (pintype "passive"))
    )
    (net (code "68") (name "Net-(U20-RX_CLK)") (class "Default")
      (node (ref "R106") (pin "1") (pinfunction "1_1") (pintype "passive"))
      (node (ref "U20") (pin "32") (pinfunction "RX_CLK_32") (pintype "output"))
    )
    (net (code "69") (name "Net-(U20-RX_CTRL)") (class "Default")
      (node (ref "R108") (pin "1") (pinfunction "1_1") (pintype "passive"))
      (node (ref "U20") (pin "38") (pinfunction "RX_CTRL_38") (pintype "output"))
    )
    (net (code "70") (name "Net-(U20-RX_D0)") (class "Default")
      (node (ref "R109") (pin "1") (pinfunction "1_1") (pintype "passive"))
      (node (ref "U20") (pin "33") (pinfunction "RX_D0_33") (pintype "output"))
    )
    (net (code "71") (name "Net-(U20-RX_D1)") (class "Default")
      (node (ref "R110") (pin "1") (pinfunction "1_1") (pintype "passive"))
      (node (ref "U20") (pin "34") (pinfunction "RX_D1_34") (pintype "output"))
    )
    (net (code "72") (name "Net-(U20-RX_D2)") (class "Default")
      (node (ref "R111") (pin "1") (pinfunction "1_1") (pintype "passive"))
      (node (ref "U20") (pin "35") (pinfunction "RX_D2_35") (pintype "output"))
    )
    (net (code "73") (name "Net-(U20-RX_D3)") (class "Default")
      (node (ref "R112") (pin "1") (pinfunction "1_1") (pintype "passive"))
      (node (ref "U20") (pin "36") (pinfunction "RX_D3_36") (pintype "output"))
    )
    (net (code "74") (name "Net-(U20-TX_CTRL)") (class "Default")
      (node (ref "R115") (pin "2") (pinfunction "2_2") (pintype "passive"))
      (node (ref "U20") (pin "37") (pinfunction "TX_CTRL_37") (pintype "input"))
    )
    (net (code "75") (name "Net-(U20-TX_D0)") (class "Default")
      (node (ref "R117") (pin "2") (pinfunction "2_2") (pintype "passive"))
      (node (ref "U20") (pin "28") (pinfunction "TX_D0_28") (pintype "input"))
    )
    (net (code "76") (name "Net-(U20-TX_D1)") (class "Default")
      (node (ref "R118") (pin "2") (pinfunction "2_2") (pintype "passive"))
      (node (ref "U20") (pin "27") (pinfunction "TX_D1_27") (pintype "input"))
    )
    (net (code "77") (name "Net-(U20-TX_D2)") (class "Default")
      (node (ref "R120") (pin "2") (pinfunction "2_2") (pintype "passive"))
      (node (ref "U20") (pin "26") (pinfunction "TX_D2_26") (pintype "input"))
    )
    (net (code "78") (name "Net-(U20-TX_D3)") (class "Default")
      (node (ref "R121") (pin "2") (pinfunction "2_2") (pintype "passive"))
      (node (ref "U20") (pin "25") (pinfunction "TX_D3_25") (pintype "input"))
    )
    (net (code "79") (name "Net-(U20-X_I)") (class "Default")
      (node (ref "C178") (pin "1") (pinfunction "1_1") (pintype "passive"))
      (node (ref "U20") (pin "15") (pinfunction "X_I_15") (pintype "input"))
      (node (ref "Y2") (pin "1") (pinfunction "1_1") (pintype "passive"))
    )
    (net (code "80") (name "Net-(U20-X_O)") (class "Default")
      (node (ref "C177") (pin "1") (pinfunction "1_1") (pintype "passive"))
      (node (ref "U20") (pin "14") (pinfunction "X_O_14") (pintype "output"))
      (node (ref "Y2") (pin "2") (pinfunction "2_2") (pintype "passive"))
    )
    (net (code "81") (name "unconnected-(U20-GPIO_0-Pad39)") (class "Default")
      (node (ref "U20") (pin "39") (pinfunction "GPIO_0_39") (pintype "bidirectional"))
    )
    (net (code "82") (name "unconnected-(U20-GPIO_1-Pad40)") (class "Default")
      (node (ref "U20") (pin "40") (pinfunction "GPIO_1_40") (pintype "bidirectional"))
    )
  )
)
